# One-Transistor-FM-Super-Regen.net
KiCad netlist of a schematic drawn in EAGLE
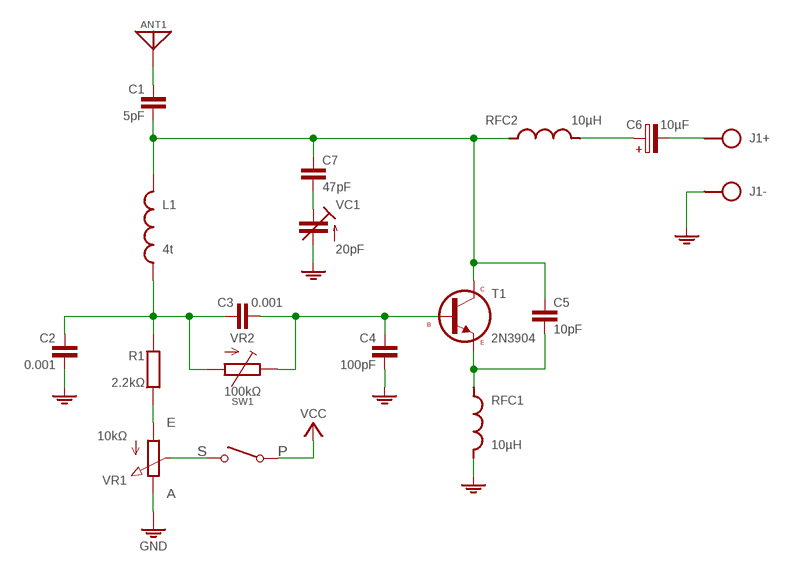
[diagram p0: schematic, sheet 1]

(export (version "E")
  (design (tool "Eeschema 10.0.6"))
  (components
    (comp (ref "ANT1")
      (value "ANT")
      (footprint "eagle-import:SPAD")
      (libsource (lib "eagle-import") (part "ANT"))
    )
    (comp (ref "C1")
      (value "5pF")
      (footprint "eagle-import:C025-015X024")
      (libsource (lib "eagle-import") (part "C025-015X024"))
    )
    (comp (ref "C2")
      (value "0.001")
      (footprint "eagle-import:C050-020X036_V")
      (libsource (lib "eagle-import") (part "C050-020X036/V"))
    )
    (comp (ref "C3")
      (value "0.001")
      (footprint "eagle-import:C050-020X036")
      (libsource (lib "eagle-import") (part "C-H050-020X036"))
    )
    (comp (ref "C4")
      (value "100pF")
      (footprint "eagle-import:C050-020X036_V")
      (libsource (lib "eagle-import") (part "C050-020X036/V"))
    )
    (comp (ref "C5")
      (value "10pF")
      (footprint "eagle-import:C050-020X036_V")
      (libsource (lib "eagle-import") (part "C050-020X036/V"))
    )
    (comp (ref "C6")
      (value "10µF")
      (footprint "eagle-import:E2,5-4")
      (libsource (lib "eagle-import") (part "CPOL-HE2,5-4"))
    )
    (comp (ref "C7")
      (value "47pF")
      (footprint "eagle-import:C025-015X024")
      (libsource (lib "eagle-import") (part "C025-015X024"))
    )
    (comp (ref "J1")
      (value "SPAD+-+-")
      (footprint "eagle-import:SPAD+-")
      (libsource (lib "eagle-import") (part "SPAD+-+-"))
    )
    (comp (ref "L1")
      (value "4t")
      (footprint "eagle-import:L-04_7-V")
      (libsource (lib "eagle-import") (part "L04/7-V"))
    )
    (comp (ref "R1")
      (value "2.2kΩ")
      (footprint "eagle-import:0204_10-V")
      (libsource (lib "eagle-import") (part "R0204/10-V"))
    )
    (comp (ref "RFC1")
      (value "10µH")
      (footprint "eagle-import:L-04-2_5V")
      (libsource (lib "eagle-import") (part "L-SHORT04-2/5V"))
    )
    (comp (ref "RFC2")
      (value "10µH")
      (footprint "eagle-import:L-03_10")
      (libsource (lib "eagle-import") (part "L-H-SHORT-03/10"))
    )
    (comp (ref "S6")
      (value "VCC_GNDPWR-R")
      (footprint "eagle-import:PWR-R")
      (libsource (lib "eagle-import") (part "VCC_GNDPWR-R"))
    )
    (comp (ref "SW1")
      (value "SW-SPST-SL-1P2T-H")
      (footprint "eagle-import:SLSW-1P2T-H")
      (libsource (lib "eagle-import") (part "SW-SPST-SL-1P2T-H"))
    )
    (comp (ref "T1")
      (value "2N3904")
      (footprint "eagle-import:TO92")
      (libsource (lib "eagle-import") (part "2N3904"))
    )
    (comp (ref "VC1")
      (value "20pF")
      (footprint "eagle-import:TRIM-2222-808")
      (libsource (lib "eagle-import") (part "C-TR-PH20127"))
    )
    (comp (ref "VR1")
      (value "10kΩ")
      (footprint "eagle-import:TRIM-POT")
      (libsource (lib "eagle-import") (part "POT-TRIM"))
    )
    (comp (ref "VR2")
      (value "100kΩ")
      (footprint "eagle-import:TRIM-POT")
      (libsource (lib "eagle-import") (part "TRIM-2-TR-3TO2"))
    )
  )
  (nets
    (net (code "1") (name "GND") (class "Default")
      (node (ref "C2") (pin "2") (pinfunction "2_2") (pintype "passive"))
      (node (ref "C4") (pin "2") (pinfunction "2_2") (pintype "passive"))
      (node (ref "J1") (pin "1") (pinfunction "P$1_1") (pintype "passive"))
      (node (ref "RFC1") (pin "1") (pinfunction "1_1") (pintype "passive"))
      (node (ref "S6") (pin "1") (pinfunction "GND_1") (pintype "power_in"))
      (node (ref "VC1") (pin "1") (pinfunction "A_1") (pintype "passive"))
      (node (ref "VC1") (pin "3") (pinfunction "A_3") (pintype "passive"))
      (node (ref "VR1") (pin "E") (pinfunction "E_E") (pintype "passive"))
    )
    (net (code "2") (name "Net-(ANT1-Pad1)") (class "Default")
      (node (ref "ANT1") (pin "1") (pinfunction "1_1") (pintype "output"))
      (node (ref "C1") (pin "1") (pinfunction "1_1") (pintype "passive"))
    )
    (net (code "3") (name "Net-(C6-Pad+)") (class "Default")
      (node (ref "C6") (pin "+") (pinfunction "+_+") (pintype "passive"))
      (node (ref "RFC2") (pin "1") (pinfunction "1_1") (pintype "passive"))
    )
    (net (code "4") (name "Net-(J1A-P$1)") (class "Default")
      (node (ref "C6") (pin "-") (pinfunction "-_-") (pintype "passive"))
      (node (ref "J1") (pin "2") (pinfunction "P$1_2") (pintype "passive"))
    )
    (net (code "5") (name "Net-(R1-1)") (class "Default")
      (node (ref "R1") (pin "2") (pinfunction "1_2") (pintype "passive"))
      (node (ref "VR1") (pin "A") (pinfunction "A_A") (pintype "passive"))
    )
    (net (code "6") (name "Net-(R1-2)") (class "Default")
      (node (ref "C2") (pin "1") (pinfunction "1_1") (pintype "passive"))
      (node (ref "C3") (pin "1") (pinfunction "1_1") (pintype "passive"))
      (node (ref "L1") (pin "2") (pinfunction "2_2") (pintype "passive"))
      (node (ref "R1") (pin "1") (pinfunction "2_1") (pintype "passive"))
      (node (ref "VR2") (pin "E") (pinfunction "2_E") (pintype "passive"))
      (node (ref "VR2") (pin "S") (pinfunction "2_S") (pintype "passive"))
    )
    (net (code "7") (name "Net-(S6A-VCC)") (class "Default")
      (node (ref "S6") (pin "2") (pinfunction "VCC_2") (pintype "power_in"))
      (node (ref "SW1") (pin "P") (pinfunction "P_P") (pintype "passive"))
    )
    (net (code "8") (name "Net-(SW1-PadS)") (class "Default")
      (node (ref "SW1") (pin "S") (pinfunction "S_S") (pintype "passive"))
      (node (ref "VR1") (pin "S") (pinfunction "S_S") (pintype "passive"))
    )
    (net (code "9") (name "Net-(T1-B)") (class "Default")
      (node (ref "C3") (pin "2") (pinfunction "2_2") (pintype "passive"))
      (node (ref "C4") (pin "1") (pinfunction "1_1") (pintype "passive"))
      (node (ref "T1") (pin "2") (pinfunction "B_2") (pintype "passive"))
      (node (ref "VR2") (pin "A") (pinfunction "1_A") (pintype "passive"))
    )
    (net (code "10") (name "Net-(T1-C)") (class "Default")
      (node (ref "C1") (pin "2") (pinfunction "2_2") (pintype "passive"))
      (node (ref "C5") (pin "1") (pinfunction "1_1") (pintype "passive"))
      (node (ref "C7") (pin "1") (pinfunction "1_1") (pintype "passive"))
      (node (ref "L1") (pin "1") (pinfunction "1_1") (pintype "passive"))
      (node (ref "RFC2") (pin "2") (pinfunction "2_2") (pintype "passive"))
      (node (ref "T1") (pin "3") (pinfunction "C_3") (pintype "passive"))
    )
    (net (code "11") (name "Net-(T1-E)") (class "Default")
      (node (ref "C5") (pin "2") (pinfunction "2_2") (pintype "passive"))
      (node (ref "RFC1") (pin "2") (pinfunction "2_2") (pintype "passive"))
      (node (ref "T1") (pin "1") (pinfunction "E_1") (pintype "passive"))
    )
    (net (code "12") (name "Net-(VC1-E)") (class "Default")
      (node (ref "C7") (pin "2") (pinfunction "2_2") (pintype "passive"))
      (node (ref "VC1") (pin "2") (pinfunction "E_2") (pintype "passive"))
    )
  )
)
